# dLatch.net
KiCad netlist of a schematic drawn in EAGLE
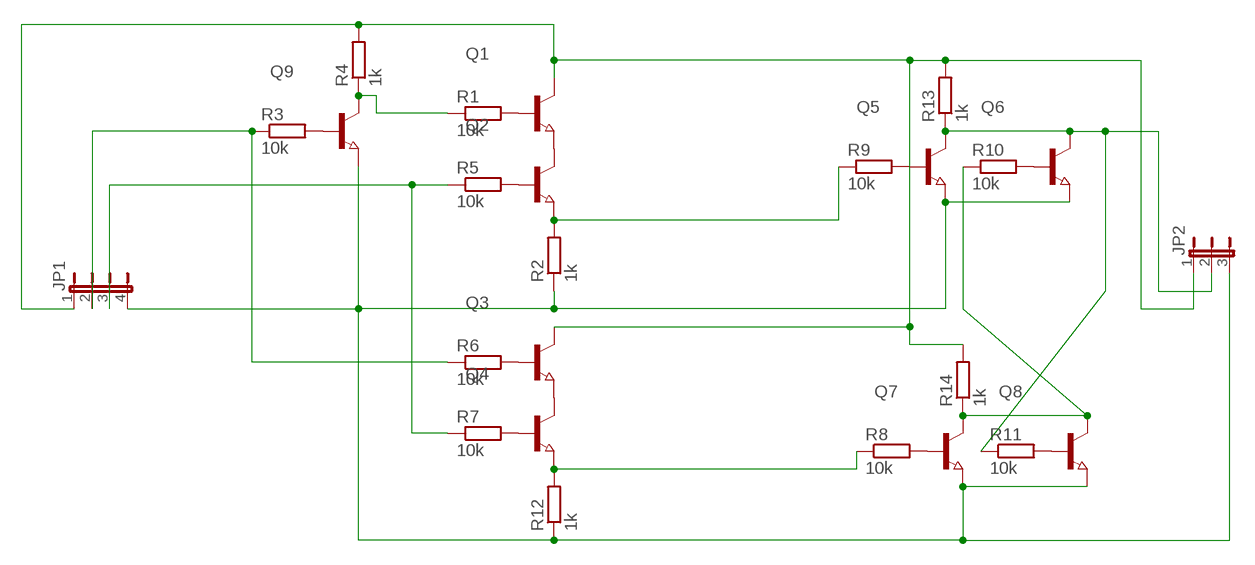
[diagram p0: schematic, sheet 1]

(export (version "E")
  (design (tool "Eeschema 10.0.6"))
  (components
    (comp (ref "JP1")
      (value "JP4E")
      (footprint "eagle-import:JP4")
      (libsource (lib "eagle-import") (part "JP4E"))
    )
    (comp (ref "JP2")
      (value "JP2W")
      (footprint "eagle-import:JP2W")
      (libsource (lib "eagle-import") (part "JP2W"))
    )
    (comp (ref "Q1")
      (value "NPN-TRANSISTOR_SOT23")
      (footprint "eagle-import:SOT23")
      (libsource (lib "eagle-import") (part "NPN-TRANSISTOR_SOT23"))
    )
    (comp (ref "Q2")
      (value "NPN-TRANSISTOR_SOT23")
      (footprint "eagle-import:SOT23")
      (libsource (lib "eagle-import") (part "NPN-TRANSISTOR_SOT23"))
    )
    (comp (ref "Q3")
      (value "NPN-TRANSISTOR_SOT23")
      (footprint "eagle-import:SOT23")
      (libsource (lib "eagle-import") (part "NPN-TRANSISTOR_SOT23"))
    )
    (comp (ref "Q4")
      (value "NPN-TRANSISTOR_SOT23")
      (footprint "eagle-import:SOT23")
      (libsource (lib "eagle-import") (part "NPN-TRANSISTOR_SOT23"))
    )
    (comp (ref "Q5")
      (value "NPN-TRANSISTOR_SOT23")
      (footprint "eagle-import:SOT23")
      (libsource (lib "eagle-import") (part "NPN-TRANSISTOR_SOT23"))
    )
    (comp (ref "Q6")
      (value "NPN-TRANSISTOR_SOT23")
      (footprint "eagle-import:SOT23")
      (libsource (lib "eagle-import") (part "NPN-TRANSISTOR_SOT23"))
    )
    (comp (ref "Q7")
      (value "NPN-TRANSISTOR_SOT23")
      (footprint "eagle-import:SOT23")
      (libsource (lib "eagle-import") (part "NPN-TRANSISTOR_SOT23"))
    )
    (comp (ref "Q8")
      (value "NPN-TRANSISTOR_SOT23")
      (footprint "eagle-import:SOT23")
      (libsource (lib "eagle-import") (part "NPN-TRANSISTOR_SOT23"))
    )
    (comp (ref "Q9")
      (value "NPN-TRANSISTOR_SOT23")
      (footprint "eagle-import:SOT23")
      (libsource (lib "eagle-import") (part "NPN-TRANSISTOR_SOT23"))
    )
    (comp (ref "R1")
      (value "10k")
      (footprint "eagle-import:R1206")
      (libsource (lib "eagle-import") (part "R-EU_R1206"))
    )
    (comp (ref "R2")
      (value "1k")
      (footprint "eagle-import:R1206")
      (libsource (lib "eagle-import") (part "R-EU_R1206"))
    )
    (comp (ref "R3")
      (value "10k")
      (footprint "eagle-import:R1206")
      (libsource (lib "eagle-import") (part "R-EU_R1206"))
    )
    (comp (ref "R4")
      (value "1k")
      (footprint "eagle-import:R1206")
      (libsource (lib "eagle-import") (part "R-EU_R1206"))
    )
    (comp (ref "R5")
      (value "10k")
      (footprint "eagle-import:R1206")
      (libsource (lib "eagle-import") (part "R-EU_R1206"))
    )
    (comp (ref "R6")
      (value "10k")
      (footprint "eagle-import:R1206")
      (libsource (lib "eagle-import") (part "R-EU_R1206"))
    )
    (comp (ref "R7")
      (value "10k")
      (footprint "eagle-import:R1206")
      (libsource (lib "eagle-import") (part "R-EU_R1206"))
    )
    (comp (ref "R8")
      (value "10k")
      (footprint "eagle-import:R1206")
      (libsource (lib "eagle-import") (part "R-EU_R1206"))
    )
    (comp (ref "R9")
      (value "10k")
      (footprint "eagle-import:R1206")
      (libsource (lib "eagle-import") (part "R-EU_R1206"))
    )
    (comp (ref "R10")
      (value "10k")
      (footprint "eagle-import:R1206")
      (libsource (lib "eagle-import") (part "R-EU_R1206"))
    )
    (comp (ref "R11")
      (value "10k")
      (footprint "eagle-import:R1206")
      (libsource (lib "eagle-import") (part "R-EU_R1206"))
    )
    (comp (ref "R12")
      (value "1k")
      (footprint "eagle-import:R1206")
      (libsource (lib "eagle-import") (part "R-EU_R1206"))
    )
    (comp (ref "R13")
      (value "1k")
      (footprint "eagle-import:R1206")
      (libsource (lib "eagle-import") (part "R-EU_R1206"))
    )
    (comp (ref "R14")
      (value "1k")
      (footprint "eagle-import:R1206")
      (libsource (lib "eagle-import") (part "R-EU_R1206"))
    )
  )
  (nets
    (net (code "1") (name "Net-(JP1-Pad2)") (class "Default")
      (node (ref "JP1") (pin "2") (pinfunction "2_2") (pintype "passive"))
      (node (ref "R3") (pin "1") (pinfunction "1_1") (pintype "passive"))
      (node (ref "R6") (pin "1") (pinfunction "1_1") (pintype "passive"))
    )
    (net (code "2") (name "Net-(JP1-Pad3)") (class "Default")
      (node (ref "JP1") (pin "3") (pinfunction "3_3") (pintype "passive"))
      (node (ref "R5") (pin "1") (pinfunction "1_1") (pintype "passive"))
      (node (ref "R7") (pin "1") (pinfunction "1_1") (pintype "passive"))
    )
    (net (code "3") (name "Net-(Q1-B)") (class "Default")
      (node (ref "Q1") (pin "1") (pinfunction "B_1") (pintype "passive"))
      (node (ref "R1") (pin "2") (pinfunction "2_2") (pintype "passive"))
    )
    (net (code "4") (name "Net-(Q1-C)") (class "Default")
      (node (ref "JP1") (pin "1") (pinfunction "1_1") (pintype "passive"))
      (node (ref "JP2") (pin "1") (pinfunction "1_1") (pintype "passive"))
      (node (ref "Q1") (pin "3") (pinfunction "C_3") (pintype "passive"))
      (node (ref "Q3") (pin "3") (pinfunction "C_3") (pintype "passive"))
      (node (ref "R13") (pin "2") (pinfunction "2_2") (pintype "passive"))
      (node (ref "R14") (pin "2") (pinfunction "2_2") (pintype "passive"))
      (node (ref "R4") (pin "2") (pinfunction "2_2") (pintype "passive"))
    )
    (net (code "5") (name "Net-(Q1-E)") (class "Default")
      (node (ref "Q1") (pin "2") (pinfunction "E_2") (pintype "passive"))
      (node (ref "Q2") (pin "3") (pinfunction "C_3") (pintype "passive"))
    )
    (net (code "6") (name "Net-(Q2-B)") (class "Default")
      (node (ref "Q2") (pin "1") (pinfunction "B_1") (pintype "passive"))
      (node (ref "R5") (pin "2") (pinfunction "2_2") (pintype "passive"))
    )
    (net (code "7") (name "Net-(Q2-E)") (class "Default")
      (node (ref "Q2") (pin "2") (pinfunction "E_2") (pintype "passive"))
      (node (ref "R2") (pin "2") (pinfunction "2_2") (pintype "passive"))
      (node (ref "R9") (pin "1") (pinfunction "1_1") (pintype "passive"))
    )
    (net (code "8") (name "Net-(Q3-B)") (class "Default")
      (node (ref "Q3") (pin "1") (pinfunction "B_1") (pintype "passive"))
      (node (ref "R6") (pin "2") (pinfunction "2_2") (pintype "passive"))
    )
    (net (code "9") (name "Net-(Q3-E)") (class "Default")
      (node (ref "Q3") (pin "2") (pinfunction "E_2") (pintype "passive"))
      (node (ref "Q4") (pin "3") (pinfunction "C_3") (pintype "passive"))
    )
    (net (code "10") (name "Net-(Q4-B)") (class "Default")
      (node (ref "Q4") (pin "1") (pinfunction "B_1") (pintype "passive"))
      (node (ref "R7") (pin "2") (pinfunction "2_2") (pintype "passive"))
    )
    (net (code "11") (name "Net-(Q4-E)") (class "Default")
      (node (ref "Q4") (pin "2") (pinfunction "E_2") (pintype "passive"))
      (node (ref "R12") (pin "2") (pinfunction "2_2") (pintype "passive"))
      (node (ref "R8") (pin "1") (pinfunction "1_1") (pintype "passive"))
    )
    (net (code "12") (name "Net-(Q5-B)") (class "Default")
      (node (ref "Q5") (pin "1") (pinfunction "B_1") (pintype "passive"))
      (node (ref "R9") (pin "2") (pinfunction "2_2") (pintype "passive"))
    )
    (net (code "13") (name "Net-(Q5-C)") (class "Default")
      (node (ref "JP2") (pin "2") (pinfunction "2_2") (pintype "passive"))
      (node (ref "Q5") (pin "3") (pinfunction "C_3") (pintype "passive"))
      (node (ref "Q6") (pin "3") (pinfunction "C_3") (pintype "passive"))
      (node (ref "R11") (pin "1") (pinfunction "1_1") (pintype "passive"))
      (node (ref "R13") (pin "1") (pinfunction "1_1") (pintype "passive"))
    )
    (net (code "14") (name "Net-(Q5-E)") (class "Default")
      (node (ref "JP1") (pin "4") (pinfunction "4_4") (pintype "passive"))
      (node (ref "JP2") (pin "3") (pinfunction "3_3") (pintype "passive"))
      (node (ref "Q5") (pin "2") (pinfunction "E_2") (pintype "passive"))
      (node (ref "Q6") (pin "2") (pinfunction "E_2") (pintype "passive"))
      (node (ref "Q7") (pin "2") (pinfunction "E_2") (pintype "passive"))
      (node (ref "Q8") (pin "2") (pinfunction "E_2") (pintype "passive"))
      (node (ref "Q9") (pin "2") (pinfunction "E_2") (pintype "passive"))
      (node (ref "R12") (pin "1") (pinfunction "1_1") (pintype "passive"))
      (node (ref "R2") (pin "1") (pinfunction "1_1") (pintype "passive"))
    )
    (net (code "15") (name "Net-(Q6-B)") (class "Default")
      (node (ref "Q6") (pin "1") (pinfunction "B_1") (pintype "passive"))
      (node (ref "R10") (pin "2") (pinfunction "2_2") (pintype "passive"))
    )
    (net (code "16") (name "Net-(Q7-B)") (class "Default")
      (node (ref "Q7") (pin "1") (pinfunction "B_1") (pintype "passive"))
      (node (ref "R8") (pin "2") (pinfunction "2_2") (pintype "passive"))
    )
    (net (code "17") (name "Net-(Q7-C)") (class "Default")
      (node (ref "Q7") (pin "3") (pinfunction "C_3") (pintype "passive"))
      (node (ref "Q8") (pin "3") (pinfunction "C_3") (pintype "passive"))
      (node (ref "R10") (pin "1") (pinfunction "1_1") (pintype "passive"))
      (node (ref "R14") (pin "1") (pinfunction "1_1") (pintype "passive"))
    )
    (net (code "18") (name "Net-(Q8-B)") (class "Default")
      (node (ref "Q8") (pin "1") (pinfunction "B_1") (pintype "passive"))
      (node (ref "R11") (pin "2") (pinfunction "2_2") (pintype "passive"))
    )
    (net (code "19") (name "Net-(Q9-B)") (class "Default")
      (node (ref "Q9") (pin "1") (pinfunction "B_1") (pintype "passive"))
      (node (ref "R3") (pin "2") (pinfunction "2_2") (pintype "passive"))
    )
    (net (code "20") (name "Net-(Q9-C)") (class "Default")
      (node (ref "Q9") (pin "3") (pinfunction "C_3") (pintype "passive"))
      (node (ref "R1") (pin "1") (pinfunction "1_1") (pintype "passive"))
      (node (ref "R4") (pin "1") (pinfunction "1_1") (pintype "passive"))
    )
  )
)
